# 20_V2X_MODEM.net
KiCad netlist of a schematic drawn in Altium Designer
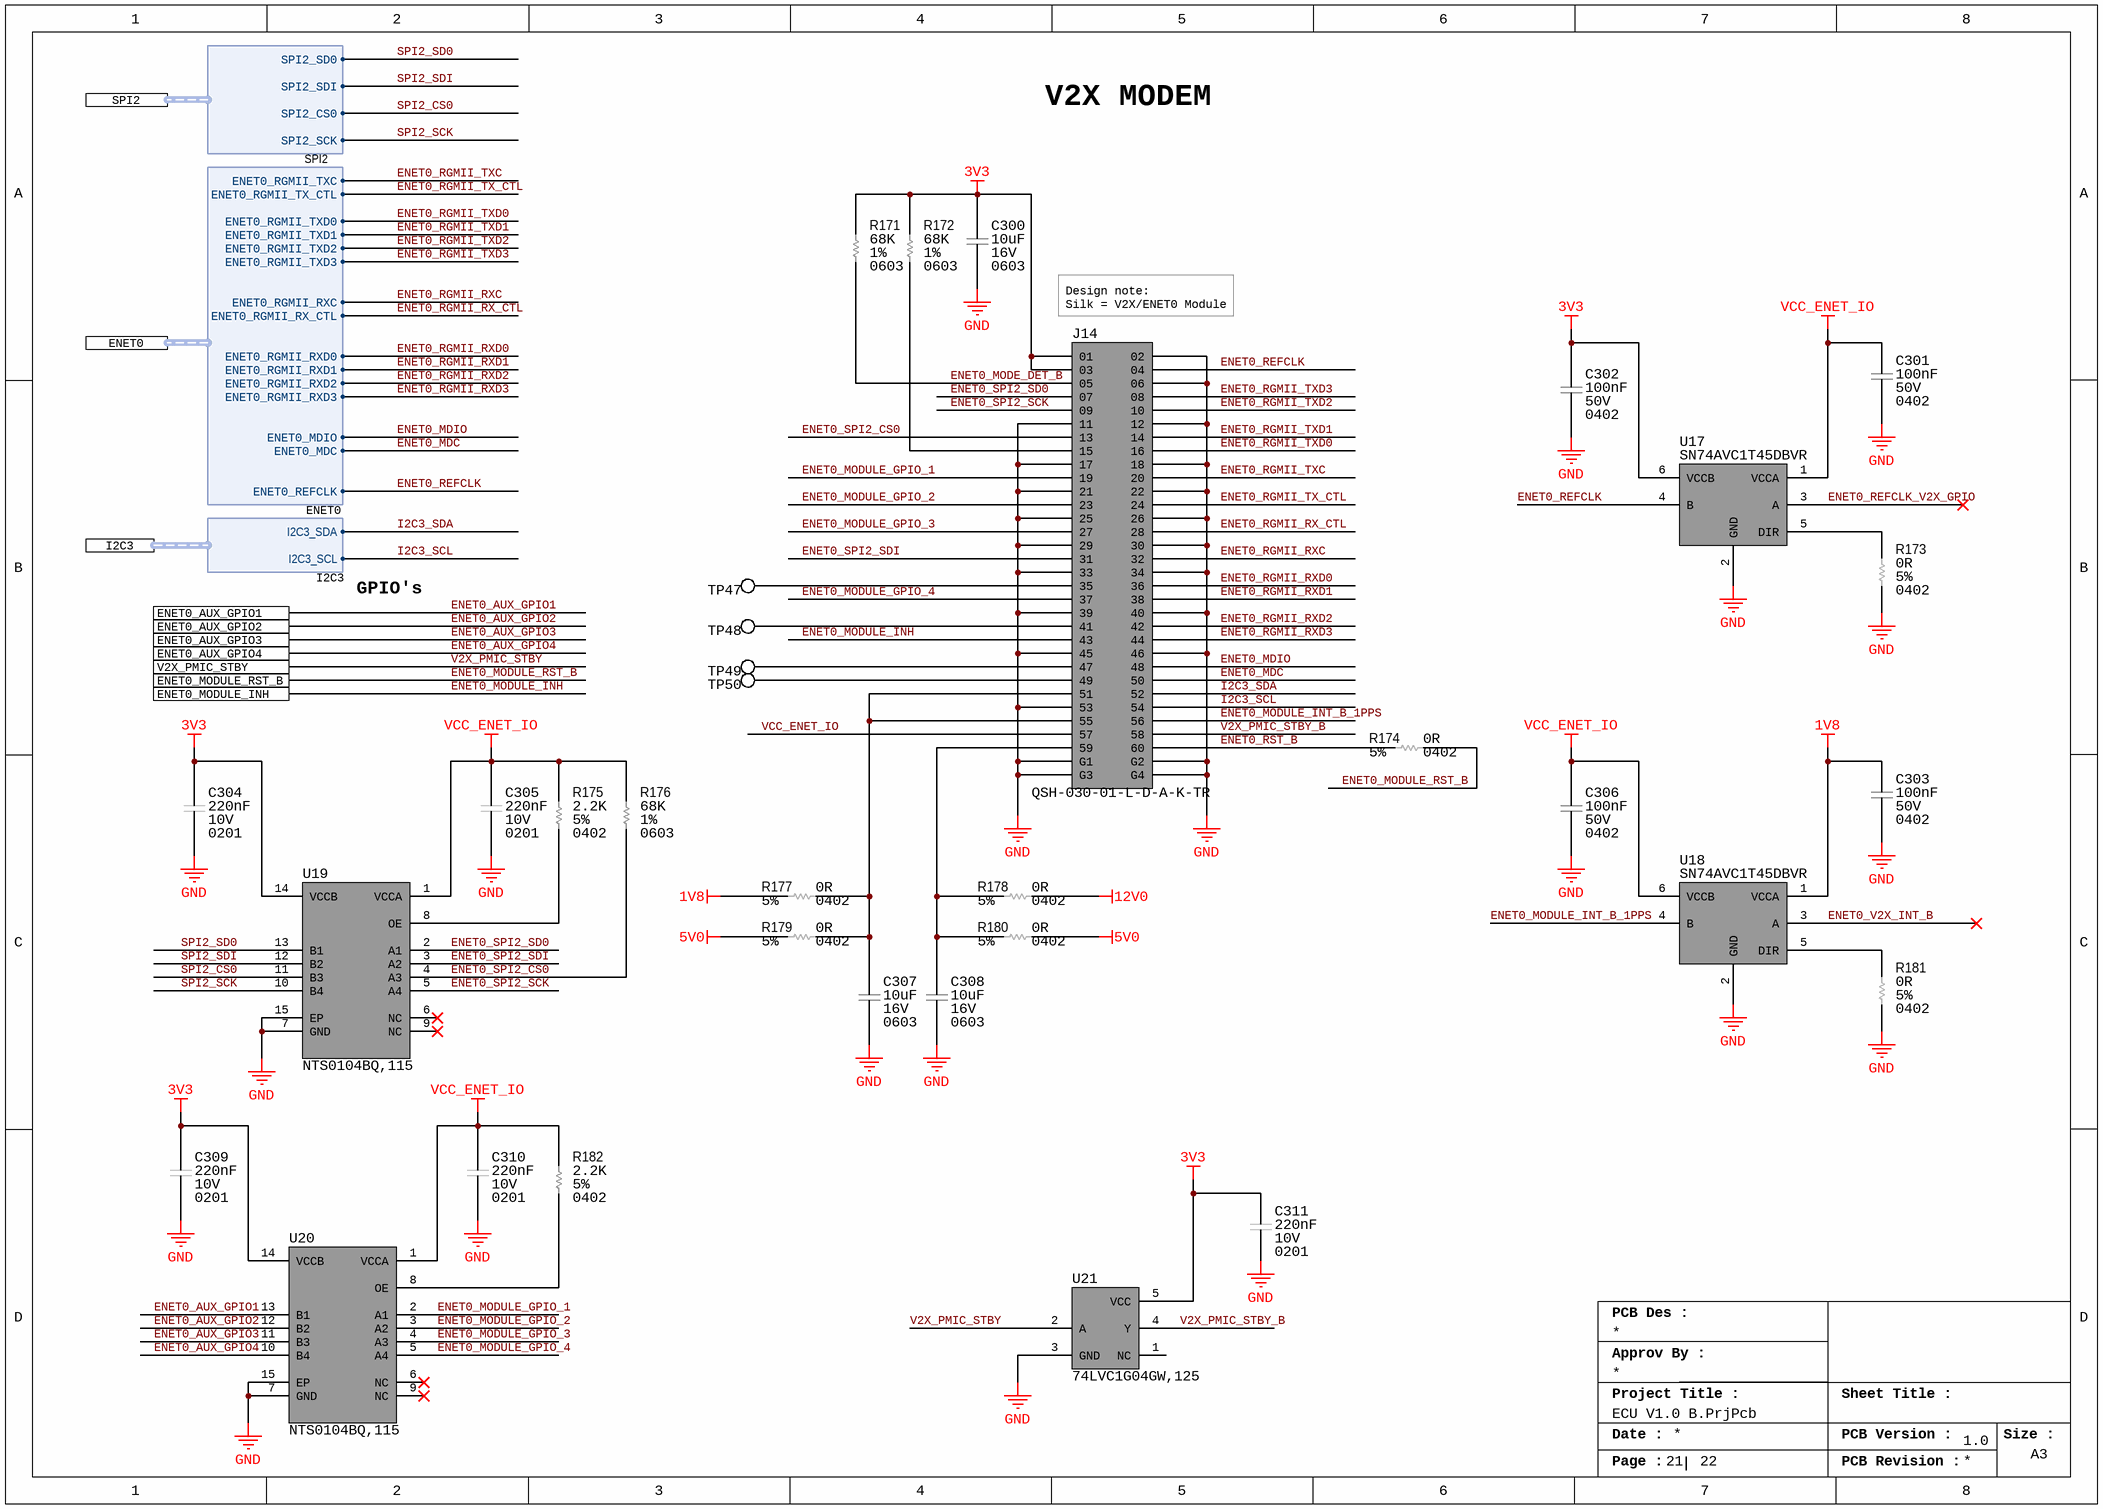
[diagram p0: 20_V2X_MODEM.SchDoc]

(export (version "E")
  (design (tool "Eeschema 10.0.6"))
  (components
    (comp (ref "C300")
      (value "GRM188R61C106MAALD")
      (footprint "CAP_0603_CAPC1608X08N")
      (description "0603 10 uF 16 V ±20% Tolerance X5R Multilayer Ceramic Chip Capacitor")
      (fields
        (field (name "MANUFACTURER") "Murata")
        (field (name "TOLERANCE") "20%")
        (field (name "VOLTAGE RATING") "16V")
        (field (name "CAPACITANCE") "10uF")
        (field (name "CASE/PACKAGE") "0603")
      )
      (libsource (lib "Electronic Devices_LIB") (part "CAP_10UF_16V_X5R_0603"))
    )
    (comp (ref "C301")
      (value "GRM155R71H104KE14D")
      (footprint "CAP_0402_CAPC1005X05N")
      (description "Multilayer Ceramic Capacitor, 0.1 uF, 16 V, ± 10%, X7R, 0402 [1005 Metric]")
      (fields
        (field (name "MANUFACTURER") "Murata")
        (field (name "TOLERANCE") "10%")
        (field (name "VOLTAGE RATING") "50V")
        (field (name "CAPACITANCE") "100nF")
        (field (name "CASE/PACKAGE") "0402")
      )
      (libsource (lib "Electronic Devices_LIB") (part "CAP_100NF_50V_X7R_0402"))
    )
    (comp (ref "C302")
      (value "GRM155R71H104KE14D")
      (footprint "CAP_0402_CAPC1005X05N")
      (description "Multilayer Ceramic Capacitor, 0.1 uF, 16 V, ± 10%, X7R, 0402 [1005 Metric]")
      (fields
        (field (name "MANUFACTURER") "Murata")
        (field (name "TOLERANCE") "10%")
        (field (name "VOLTAGE RATING") "50V")
        (field (name "CAPACITANCE") "100nF")
        (field (name "CASE/PACKAGE") "0402")
      )
      (libsource (lib "Electronic Devices_LIB") (part "CAP_100NF_50V_X7R_0402"))
    )
    (comp (ref "C303")
      (value "GRM155R71H104KE14D")
      (footprint "CAP_0402_CAPC1005X05N")
      (description "Multilayer Ceramic Capacitor, 0.1 uF, 16 V, ± 10%, X7R, 0402 [1005 Metric]")
      (fields
        (field (name "MANUFACTURER") "Murata")
        (field (name "TOLERANCE") "10%")
        (field (name "VOLTAGE RATING") "50V")
        (field (name "CAPACITANCE") "100nF")
        (field (name "CASE/PACKAGE") "0402")
      )
      (libsource (lib "Electronic Devices_LIB") (part "CAP_100NF_50V_X7R_0402"))
    )
    (comp (ref "C304")
      (value "LMK063BJ224MP-F")
      (footprint "CAP_0201_CAPC0603X03N")
      (description "Multilayer Ceramic Capacitors (High dielectric type), 10V, 0.22 uF, ± 20 %, 0201, X5R, RoHS")
      (fields
        (field (name "MANUFACTURER") "Taiyo Yuden")
        (field (name "TOLERANCE") "20%")
        (field (name "VOLTAGE RATING (DC)") "10V")
        (field (name "CAPACITANCE") "220nF")
        (field (name "CASE/PACKAGE") "0201")
      )
      (libsource (lib "Electronic Devices_LIB") (part "CAP_0.22UF_10V_X5R_0201"))
    )
    (comp (ref "C305")
      (value "LMK063BJ224MP-F")
      (footprint "CAP_0201_CAPC0603X03N")
      (description "Multilayer Ceramic Capacitors (High dielectric type), 10V, 0.22 uF, ± 20 %, 0201, X5R, RoHS")
      (fields
        (field (name "MANUFACTURER") "Taiyo Yuden")
        (field (name "TOLERANCE") "20%")
        (field (name "VOLTAGE RATING (DC)") "10V")
        (field (name "CAPACITANCE") "220nF")
        (field (name "CASE/PACKAGE") "0201")
      )
      (libsource (lib "Electronic Devices_LIB") (part "CAP_0.22UF_10V_X5R_0201"))
    )
    (comp (ref "C306")
      (value "GRM155R71H104KE14D")
      (footprint "CAP_0402_CAPC1005X05N")
      (description "Multilayer Ceramic Capacitor, 0.1 uF, 16 V, ± 10%, X7R, 0402 [1005 Metric]")
      (fields
        (field (name "MANUFACTURER") "Murata")
        (field (name "TOLERANCE") "10%")
        (field (name "VOLTAGE RATING") "50V")
        (field (name "CAPACITANCE") "100nF")
        (field (name "CASE/PACKAGE") "0402")
      )
      (libsource (lib "Electronic Devices_LIB") (part "CAP_100NF_50V_X7R_0402"))
    )
    (comp (ref "C307")
      (value "GRM188R61C106MAALD")
      (footprint "CAP_0603_CAPC1608X08N")
      (description "0603 10 uF 16 V ±20% Tolerance X5R Multilayer Ceramic Chip Capacitor")
      (fields
        (field (name "MANUFACTURER") "Murata")
        (field (name "TOLERANCE") "20%")
        (field (name "VOLTAGE RATING") "16V")
        (field (name "CAPACITANCE") "10uF")
        (field (name "CASE/PACKAGE") "0603")
      )
      (libsource (lib "Electronic Devices_LIB") (part "CAP_10UF_16V_X5R_0603"))
    )
    (comp (ref "C308")
      (value "GRM188R61C106MAALD")
      (footprint "CAP_0603_CAPC1608X08N")
      (description "0603 10 uF 16 V ±20% Tolerance X5R Multilayer Ceramic Chip Capacitor")
      (fields
        (field (name "MANUFACTURER") "Murata")
        (field (name "TOLERANCE") "20%")
        (field (name "VOLTAGE RATING") "16V")
        (field (name "CAPACITANCE") "10uF")
        (field (name "CASE/PACKAGE") "0603")
      )
      (libsource (lib "Electronic Devices_LIB") (part "CAP_10UF_16V_X5R_0603"))
    )
    (comp (ref "C309")
      (value "LMK063BJ224MP-F")
      (footprint "CAP_0201_CAPC0603X03N")
      (description "Multilayer Ceramic Capacitors (High dielectric type), 10V, 0.22 uF, ± 20 %, 0201, X5R, RoHS")
      (fields
        (field (name "MANUFACTURER") "Taiyo Yuden")
        (field (name "TOLERANCE") "20%")
        (field (name "VOLTAGE RATING (DC)") "10V")
        (field (name "CAPACITANCE") "220nF")
        (field (name "CASE/PACKAGE") "0201")
      )
      (libsource (lib "Electronic Devices_LIB") (part "CAP_0.22UF_10V_X5R_0201"))
    )
    (comp (ref "C310")
      (value "LMK063BJ224MP-F")
      (footprint "CAP_0201_CAPC0603X03N")
      (description "Multilayer Ceramic Capacitors (High dielectric type), 10V, 0.22 uF, ± 20 %, 0201, X5R, RoHS")
      (fields
        (field (name "MANUFACTURER") "Taiyo Yuden")
        (field (name "TOLERANCE") "20%")
        (field (name "VOLTAGE RATING (DC)") "10V")
        (field (name "CAPACITANCE") "220nF")
        (field (name "CASE/PACKAGE") "0201")
      )
      (libsource (lib "Electronic Devices_LIB") (part "CAP_0.22UF_10V_X5R_0201"))
    )
    (comp (ref "C311")
      (value "LMK063BJ224MP-F")
      (footprint "CAP_0201_CAPC0603X03N")
      (description "Multilayer Ceramic Capacitors (High dielectric type), 10V, 0.22 uF, ± 20 %, 0201, X5R, RoHS")
      (fields
        (field (name "MANUFACTURER") "Taiyo Yuden")
        (field (name "TOLERANCE") "20%")
        (field (name "VOLTAGE RATING (DC)") "10V")
        (field (name "CAPACITANCE") "220nF")
        (field (name "CASE/PACKAGE") "0201")
      )
      (libsource (lib "Electronic Devices_LIB") (part "CAP_0.22UF_10V_X5R_0201"))
    )
    (comp (ref "J14")
      (value "QSH-030-01-L-D-A-K-TR")
      (footprint "SAMTEC_QSH-030-01-X-D-A-XX")
      (description "Board to Board & Mezzanine Connectors 0.50 mm Q Strip High-Speed Ground Plane Socket Strip")
      (fields (field (name "MANUFACTURER") "Samtec"))
      (libsource (lib "Electronic Devices_LIB") (part "CONN_MEZZANINE_60P_0.5mm_QSH-030-01-L-D-A-K-TR"))
    )
    (comp (ref "R171")
      (value "RC0603FR-0768KL")
      (footprint "RES_0603_RESC1608X04N")
      (description "SMD Chip Resistor, 68 kOhm, ± 1%, 100 mW, 0603 [1608 Metric], Thick Film, General Purpose")
      (fields
        (field (name "MANUFACTURER") "Yageo")
        (field (name "TOLERANCE") "1%")
        (field (name "RESISTANCE") "68K")
        (field (name "CASE/PACKAGE") "0603")
      )
      (libsource (lib "Electronic Devices_LIB") (part "RES_68K_1%_100mW_0603"))
    )
    (comp (ref "R172")
      (value "RC0603FR-0768KL")
      (footprint "RES_0603_RESC1608X04N")
      (description "SMD Chip Resistor, 68 kOhm, ± 1%, 100 mW, 0603 [1608 Metric], Thick Film, General Purpose")
      (fields
        (field (name "MANUFACTURER") "Yageo")
        (field (name "TOLERANCE") "1%")
        (field (name "RESISTANCE") "68K")
        (field (name "CASE/PACKAGE") "0603")
      )
      (libsource (lib "Electronic Devices_LIB") (part "RES_68K_1%_100mW_0603"))
    )
    (comp (ref "R173")
      (value "ERJ-2GE0R00X")
      (footprint "RES_0402_RESC1005X04N")
      (description "SMD Chip Resistor, Jumper, 0 ohm, 100 mW, 0402 [1005 Metric], Thick Film, General Purpose")
      (fields
        (field (name "MANUFACTURER") "Panasonic")
        (field (name "CASE CODE (IMPERIAL)") "0402")
        (field (name "TOLERANCE") "5%")
        (field (name "RESISTANCE") "0R")
      )
      (libsource (lib "Electronic Devices_LIB") (part "RES_0R_5%_100mW_0402"))
    )
    (comp (ref "R174")
      (value "ERJ-2GE0R00X")
      (footprint "RES_0402_RESC1005X04N")
      (description "SMD Chip Resistor, Jumper, 0 ohm, 100 mW, 0402 [1005 Metric], Thick Film, General Purpose")
      (fields
        (field (name "MANUFACTURER") "Panasonic")
        (field (name "CASE CODE (IMPERIAL)") "0402")
        (field (name "TOLERANCE") "5%")
        (field (name "RESISTANCE") "0R")
      )
      (libsource (lib "Electronic Devices_LIB") (part "RES_0R_5%_100mW_0402"))
    )
    (comp (ref "R175")
      (value "RC0402JR-072K2L")
      (footprint "RES_0402_RESC1005X04N")
      (description "SMD Chip Resistor, 2.2 kOhm, ± 5%, 63 mW, 0402 [1005 Metric], Thick Film, General Purpose")
      (fields
        (field (name "MANUFACTURER") "Yageo")
        (field (name "TOLERANCE") "5%")
        (field (name "RESISTANCE") "2.2K")
        (field (name "CASE/PACKAGE") "0402")
      )
      (libsource (lib "Electronic Devices_LIB") (part "RES_2.2K_5%_63mW_0402"))
    )
    (comp (ref "R176")
      (value "RC0603FR-0768KL")
      (footprint "RES_0603_RESC1608X04N")
      (description "SMD Chip Resistor, 68 kOhm, ± 1%, 100 mW, 0603 [1608 Metric], Thick Film, General Purpose")
      (fields
        (field (name "MANUFACTURER") "Yageo")
        (field (name "TOLERANCE") "1%")
        (field (name "RESISTANCE") "68K")
        (field (name "CASE/PACKAGE") "0603")
      )
      (libsource (lib "Electronic Devices_LIB") (part "RES_68K_1%_100mW_0603"))
    )
    (comp (ref "R177")
      (value "ERJ-2GE0R00X")
      (footprint "RES_0402_RESC1005X04N")
      (description "SMD Chip Resistor, Jumper, 0 ohm, 100 mW, 0402 [1005 Metric], Thick Film, General Purpose")
      (fields
        (field (name "MANUFACTURER") "Panasonic")
        (field (name "CASE CODE (IMPERIAL)") "0402")
        (field (name "TOLERANCE") "5%")
        (field (name "RESISTANCE") "0R")
      )
      (libsource (lib "Electronic Devices_LIB") (part "RES_0R_5%_100mW_0402"))
    )
    (comp (ref "R178")
      (value "ERJ-2GE0R00X")
      (footprint "RES_0402_RESC1005X04N")
      (description "SMD Chip Resistor, Jumper, 0 ohm, 100 mW, 0402 [1005 Metric], Thick Film, General Purpose")
      (fields
        (field (name "MANUFACTURER") "Panasonic")
        (field (name "CASE CODE (IMPERIAL)") "0402")
        (field (name "TOLERANCE") "5%")
        (field (name "RESISTANCE") "0R")
      )
      (libsource (lib "Electronic Devices_LIB") (part "RES_0R_5%_100mW_0402"))
    )
    (comp (ref "R179")
      (value "ERJ-2GE0R00X")
      (footprint "RES_0402_RESC1005X04N")
      (description "SMD Chip Resistor, Jumper, 0 ohm, 100 mW, 0402 [1005 Metric], Thick Film, General Purpose")
      (fields
        (field (name "MANUFACTURER") "Panasonic")
        (field (name "CASE CODE (IMPERIAL)") "0402")
        (field (name "TOLERANCE") "5%")
        (field (name "RESISTANCE") "0R")
      )
      (libsource (lib "Electronic Devices_LIB") (part "RES_0R_5%_100mW_0402"))
    )
    (comp (ref "R180")
      (value "ERJ-2GE0R00X")
      (footprint "RES_0402_RESC1005X04N")
      (description "SMD Chip Resistor, Jumper, 0 ohm, 100 mW, 0402 [1005 Metric], Thick Film, General Purpose")
      (fields
        (field (name "MANUFACTURER") "Panasonic")
        (field (name "CASE CODE (IMPERIAL)") "0402")
        (field (name "TOLERANCE") "5%")
        (field (name "RESISTANCE") "0R")
      )
      (libsource (lib "Electronic Devices_LIB") (part "RES_0R_5%_100mW_0402"))
    )
    (comp (ref "R181")
      (value "ERJ-2GE0R00X")
      (footprint "RES_0402_RESC1005X04N")
      (description "SMD Chip Resistor, Jumper, 0 ohm, 100 mW, 0402 [1005 Metric], Thick Film, General Purpose")
      (fields
        (field (name "MANUFACTURER") "Panasonic")
        (field (name "CASE CODE (IMPERIAL)") "0402")
        (field (name "TOLERANCE") "5%")
        (field (name "RESISTANCE") "0R")
      )
      (libsource (lib "Electronic Devices_LIB") (part "RES_0R_5%_100mW_0402"))
    )
    (comp (ref "R182")
      (value "RC0402JR-072K2L")
      (footprint "RES_0402_RESC1005X04N")
      (description "SMD Chip Resistor, 2.2 kOhm, ± 5%, 63 mW, 0402 [1005 Metric], Thick Film, General Purpose")
      (fields
        (field (name "MANUFACTURER") "Yageo")
        (field (name "TOLERANCE") "5%")
        (field (name "RESISTANCE") "2.2K")
        (field (name "CASE/PACKAGE") "0402")
      )
      (libsource (lib "Electronic Devices_LIB") (part "RES_2.2K_5%_63mW_0402"))
    )
    (comp (ref "TP47")
      (value "NO COMPONENT")
      (footprint "TP_PAD_0.5MM_SMD_ROUND")
      (description "Test Point, SMD pad, round, 1.5mm, 1.6mm, 3mm diameter")
      (libsource (lib "Electronic Devices_LIB") (part "TP_PAD_SMD_SMALL"))
    )
    (comp (ref "TP48")
      (value "NO COMPONENT")
      (footprint "TP_PAD_0.5MM_SMD_ROUND")
      (description "Test Point, SMD pad, round, 1.5mm, 1.6mm, 3mm diameter")
      (libsource (lib "Electronic Devices_LIB") (part "TP_PAD_SMD_SMALL"))
    )
    (comp (ref "TP49")
      (value "NO COMPONENT")
      (footprint "TP_PAD_0.5MM_SMD_ROUND")
      (description "Test Point, SMD pad, round, 1.5mm, 1.6mm, 3mm diameter")
      (libsource (lib "Electronic Devices_LIB") (part "TP_PAD_SMD_SMALL"))
    )
    (comp (ref "TP50")
      (value "NO COMPONENT")
      (footprint "TP_PAD_0.5MM_SMD_ROUND")
      (description "Test Point, SMD pad, round, 1.5mm, 1.6mm, 3mm diameter")
      (libsource (lib "Electronic Devices_LIB") (part "TP_PAD_SMD_SMALL"))
    )
    (comp (ref "U17")
      (value "SN74AVC1T45DBVR")
      (footprint "SOT95P280X145-6N")
      (description "1.2V~3.6V 1 1 1.2V~3.6V 500Mbps SOT-23-6 Translators / Level Shifters ROHS")
      (fields (field (name "MANUFACTURER") "Texas Instruments"))
      (libsource (lib "Electronic Devices_LIB") (part "IC_LEVEL_TRANSLATE_1CH_SN74AVC1T45DBVR"))
    )
    (comp (ref "U18")
      (value "SN74AVC1T45DBVR")
      (footprint "SOT95P280X145-6N")
      (description "1.2V~3.6V 1 1 1.2V~3.6V 500Mbps SOT-23-6 Translators / Level Shifters ROHS")
      (fields (field (name "MANUFACTURER") "Texas Instruments"))
      (libsource (lib "Electronic Devices_LIB") (part "IC_LEVEL_TRANSLATE_1CH_SN74AVC1T45DBVR"))
    )
    (comp (ref "U19")
      (value "NTS0104BQ,115")
      (footprint "QFN50P300X250X100-15N")
      (description "Voltage Level Translator Bidirectional 1 Circuit 4 Channel 50Mbps 14-DHVQFN (2.5x3)")
      (fields (field (name "MANUFACTURER") "NXP Semiconductors"))
      (libsource (lib "Electronic Devices_LIB") (part "IC_LEVEL_TRASLATE_4CH_NTS0104BQ,115"))
    )
    (comp (ref "U20")
      (value "NTS0104BQ,115")
      (footprint "QFN50P300X250X100-15N")
      (description "Voltage Level Translator Bidirectional 1 Circuit 4 Channel 50Mbps 14-DHVQFN (2.5x3)")
      (fields (field (name "MANUFACTURER") "NXP Semiconductors"))
      (libsource (lib "Electronic Devices_LIB") (part "IC_LEVEL_TRASLATE_4CH_NTS0104BQ,115"))
    )
    (comp (ref "U21")
      (value "74LVC1G04GW,125")
      (footprint "SOT65P210X110-5N")
      (description "74LVC Series 5.5 V Surface Mount Single Inverting Buffer - TSSOP-5")
      (fields (field (name "MANUFACTURER") "Nexperia"))
      (libsource (lib "Electronic Devices_LIB") (part "IC_INVERTER_1CH_74LVC1G04GW,125"))
    )
  )
  (nets
    (net (code "4") (name "/ENET0_AUX_GPIO1") (class "Default")
      (node (ref "U20") (pin "13") (pinfunction "B1_13") (pintype "passive"))
    )
    (net (code "5") (name "/ENET0_AUX_GPIO2") (class "Default")
      (node (ref "U20") (pin "12") (pinfunction "B2_12") (pintype "passive"))
    )
    (net (code "6") (name "/ENET0_AUX_GPIO3") (class "Default")
      (node (ref "U20") (pin "11") (pinfunction "B3_11") (pintype "passive"))
    )
    (net (code "7") (name "/ENET0_AUX_GPIO4") (class "Default")
      (node (ref "U20") (pin "10") (pinfunction "B4_10") (pintype "passive"))
    )
    (net (code "8") (name "/ENET0_MDC") (class "Default")
      (node (ref "J14") (pin "50") (pinfunction "50_50") (pintype "passive"))
    )
    (net (code "9") (name "/ENET0_MDIO") (class "Default")
      (node (ref "J14") (pin "48") (pinfunction "48_48") (pintype "passive"))
    )
    (net (code "10") (name "/ENET0_MODE_DET_B") (class "Default")
      (node (ref "J14") (pin "05") (pinfunction "05_05") (pintype "passive"))
      (node (ref "R171") (pin "1") (pinfunction "1_1") (pintype "passive"))
    )
    (net (code "11") (name "/ENET0_MODULE_GPIO_1") (class "Default")
      (node (ref "J14") (pin "19") (pinfunction "19_19") (pintype "passive"))
      (node (ref "U20") (pin "2") (pinfunction "A1_2") (pintype "passive"))
    )
    (net (code "12") (name "/ENET0_MODULE_GPIO_2") (class "Default")
      (node (ref "J14") (pin "23") (pinfunction "23_23") (pintype "passive"))
      (node (ref "U20") (pin "3") (pinfunction "A2_3") (pintype "passive"))
    )
    (net (code "13") (name "/ENET0_MODULE_GPIO_3") (class "Default")
      (node (ref "J14") (pin "27") (pinfunction "27_27") (pintype "passive"))
      (node (ref "U20") (pin "4") (pinfunction "A3_4") (pintype "passive"))
    )
    (net (code "14") (name "/ENET0_MODULE_GPIO_4") (class "Default")
      (node (ref "J14") (pin "37") (pinfunction "37_37") (pintype "passive"))
      (node (ref "U20") (pin "5") (pinfunction "A4_5") (pintype "passive"))
    )
    (net (code "15") (name "/ENET0_MODULE_INH") (class "Default")
      (node (ref "J14") (pin "43") (pinfunction "43_43") (pintype "passive"))
    )
    (net (code "16") (name "/ENET0_MODULE_INT_B_1PPS") (class "Default")
      (node (ref "J14") (pin "56") (pinfunction "56_56") (pintype "passive"))
      (node (ref "U18") (pin "4") (pinfunction "B_4") (pintype "passive"))
    )
    (net (code "17") (name "/ENET0_MODULE_RST_B") (class "Default")
      (node (ref "R174") (pin "2") (pinfunction "2_2") (pintype "passive"))
    )
    (net (code "18") (name "/ENET0_REFCLK") (class "Default")
      (node (ref "J14") (pin "04") (pinfunction "04_04") (pintype "passive"))
      (node (ref "U17") (pin "4") (pinfunction "B_4") (pintype "passive"))
    )
    (net (code "19") (name "/ENET0_REFCLK_V2X_GPIO") (class "Default")
      (node (ref "U17") (pin "3") (pinfunction "A_3") (pintype "passive+no_connect"))
    )
    (net (code "20") (name "/ENET0_RGMII_RXC") (class "Default")
      (node (ref "J14") (pin "32") (pinfunction "32_32") (pintype "passive"))
    )
    (net (code "21") (name "/ENET0_RGMII_RXD0") (class "Default")
      (node (ref "J14") (pin "36") (pinfunction "36_36") (pintype "passive"))
    )
    (net (code "22") (name "/ENET0_RGMII_RXD1") (class "Default")
      (node (ref "J14") (pin "38") (pinfunction "38_38") (pintype "passive"))
    )
    (net (code "23") (name "/ENET0_RGMII_RXD2") (class "Default")
      (node (ref "J14") (pin "42") (pinfunction "42_42") (pintype "passive"))
    )
    (net (code "24") (name "/ENET0_RGMII_RXD3") (class "Default")
      (node (ref "J14") (pin "44") (pinfunction "44_44") (pintype "passive"))
    )
    (net (code "25") (name "/ENET0_RGMII_RX_CTL") (class "Default")
      (node (ref "J14") (pin "28") (pinfunction "28_28") (pintype "passive"))
    )
    (net (code "26") (name "/ENET0_RGMII_TXC") (class "Default")
      (node (ref "J14") (pin "20") (pinfunction "20_20") (pintype "passive"))
    )
    (net (code "27") (name "/ENET0_RGMII_TXD0") (class "Default")
      (node (ref "J14") (pin "16") (pinfunction "16_16") (pintype "passive"))
    )
    (net (code "28") (name "/ENET0_RGMII_TXD1") (class "Default")
      (node (ref "J14") (pin "14") (pinfunction "14_14") (pintype "passive"))
    )
    (net (code "29") (name "/ENET0_RGMII_TXD2") (class "Default")
      (node (ref "J14") (pin "10") (pinfunction "10_10") (pintype "passive"))
    )
    (net (code "30") (name "/ENET0_RGMII_TXD3") (class "Default")
      (node (ref "J14") (pin "08") (pinfunction "08_08") (pintype "passive"))
    )
    (net (code "31") (name "/ENET0_RGMII_TX_CTL") (class "Default")
      (node (ref "J14") (pin "24") (pinfunction "24_24") (pintype "passive"))
    )
    (net (code "32") (name "/ENET0_RST_B") (class "Default")
      (node (ref "J14") (pin "60") (pinfunction "60_60") (pintype "passive"))
      (node (ref "R174") (pin "1") (pinfunction "1_1") (pintype "passive"))
    )
    (net (code "33") (name "/ENET0_SPI2_CS0") (class "Default")
      (node (ref "J14") (pin "13") (pinfunction "13_13") (pintype "passive"))
      (node (ref "R176") (pin "1") (pinfunction "1_1") (pintype "passive"))
      (node (ref "U19") (pin "4") (pinfunction "A3_4") (pintype "passive"))
    )
    (net (code "34") (name "/ENET0_SPI2_SCK") (class "Default")
      (node (ref "J14") (pin "09") (pinfunction "09_09") (pintype "passive"))
      (node (ref "U19") (pin "5") (pinfunction "A4_5") (pintype "passive"))
    )
    (net (code "35") (name "/ENET0_SPI2_SD0") (class "Default")
      (node (ref "J14") (pin "07") (pinfunction "07_07") (pintype "passive"))
      (node (ref "U19") (pin "2") (pinfunction "A1_2") (pintype "passive"))
    )
    (net (code "36") (name "/ENET0_SPI2_SDI") (class "Default")
      (node (ref "J14") (pin "31") (pinfunction "31_31") (pintype "passive"))
      (node (ref "U19") (pin "3") (pinfunction "A2_3") (pintype "passive"))
    )
    (net (code "37") (name "/ENET0_V2X_INT_B") (class "Default")
      (node (ref "U18") (pin "3") (pinfunction "A_3") (pintype "passive+no_connect"))
    )
    (net (code "38") (name "/I2C3_SCL") (class "Default")
      (node (ref "J14") (pin "54") (pinfunction "54_54") (pintype "passive"))
    )
    (net (code "39") (name "/I2C3_SDA") (class "Default")
      (node (ref "J14") (pin "52") (pinfunction "52_52") (pintype "passive"))
    )
    (net (code "40") (name "/SPI2_CS0") (class "Default")
      (node (ref "U19") (pin "11") (pinfunction "B3_11") (pintype "passive"))
    )
    (net (code "41") (name "/SPI2_SCK") (class "Default")
      (node (ref "U19") (pin "10") (pinfunction "B4_10") (pintype "passive"))
    )
    (net (code "42") (name "/SPI2_SD0") (class "Default")
      (node (ref "U19") (pin "13") (pinfunction "B1_13") (pintype "passive"))
    )
    (net (code "43") (name "/SPI2_SDI") (class "Default")
      (node (ref "U19") (pin "12") (pinfunction "B2_12") (pintype "passive"))
    )
    (net (code "44") (name "/V2X_PMIC_STBY") (class "Default")
      (node (ref "U21") (pin "2") (pinfunction "A_2") (pintype "passive"))
    )
    (net (code "45") (name "/V2X_PMIC_STBY_B") (class "Default")
      (node (ref "J14") (pin "58") (pinfunction "58_58") (pintype "passive"))
      (node (ref "U21") (pin "4") (pinfunction "Y_4") (pintype "passive"))
    )
    (net (code "49") (name "1V8") (class "Default")
      (node (ref "C303") (pin "2") (pinfunction "2_2") (pintype "passive"))
      (node (ref "R177") (pin "1") (pinfunction "1_1") (pintype "passive"))
      (node (ref "U18") (pin "1") (pinfunction "VCCA_1") (pintype "power_in"))
    )
    (net (code "50") (name "3V3") (class "Default")
      (node (ref "C300") (pin "2") (pinfunction "2_2") (pintype "passive"))
      (node (ref "C302") (pin "2") (pinfunction "2_2") (pintype "passive"))
      (node (ref "C304") (pin "1") (pinfunction "1_1") (pintype "passive"))
      (node (ref "C309") (pin "1") (pinfunction "1_1") (pintype "passive"))
      (node (ref "C311") (pin "1") (pinfunction "1_1") (pintype "passive"))
      (node (ref "J14") (pin "01") (pinfunction "01_01") (pintype "passive"))
      (node (ref "J14") (pin "03") (pinfunction "03_03") (pintype "passive"))
      (node (ref "R171") (pin "2") (pinfunction "2_2") (pintype "passive"))
      (node (ref "R172") (pin "2") (pinfunction "2_2") (pintype "passive"))
      (node (ref "U17") (pin "6") (pinfunction "VCCB_6") (pintype "power_in"))
      (node (ref "U19") (pin "14") (pinfunction "VCCB_14") (pintype "power_in"))
      (node (ref "U20") (pin "14") (pinfunction "VCCB_14") (pintype "power_in"))
      (node (ref "U21") (pin "5") (pinfunction "VCC_5") (pintype "power_in"))
    )
    (net (code "51") (name "5V0") (class "Default")
      (node (ref "R179") (pin "1") (pinfunction "1_1") (pintype "passive"))
      (node (ref "R180") (pin "2") (pinfunction "2_2") (pintype "passive"))
    )
    (net (code "52") (name "12V0") (class "Default")
      (node (ref "R178") (pin "2") (pinfunction "2_2") (pintype "passive"))
    )
    (net (code "53") (name "GND") (class "Default")
      (node (ref "C300") (pin "1") (pinfunction "1_1") (pintype "passive"))
      (node (ref "C301") (pin "1") (pinfunction "1_1") (pintype "passive"))
      (node (ref "C302") (pin "1") (pinfunction "1_1") (pintype "passive"))
      (node (ref "C303") (pin "1") (pinfunction "1_1") (pintype "passive"))
      (node (ref "C304") (pin "2") (pinfunction "2_2") (pintype "passive"))
      (node (ref "C305") (pin "2") (pinfunction "2_2") (pintype "passive"))
      (node (ref "C306") (pin "1") (pinfunction "1_1") (pintype "passive"))
      (node (ref "C307") (pin "1") (pinfunction "1_1") (pintype "passive"))
      (node (ref "C308") (pin "1") (pinfunction "1_1") (pintype "passive"))
      (node (ref "C309") (pin "2") (pinfunction "2_2") (pintype "passive"))
      (node (ref "C310") (pin "2") (pinfunction "2_2") (pintype "passive"))
      (node (ref "C311") (pin "2") (pinfunction "2_2") (pintype "passive"))
      (node (ref "J14") (pin "02") (pinfunction "02_02") (pintype "passive"))
      (node (ref "J14") (pin "06") (pinfunction "06_06") (pintype "passive"))
      (node (ref "J14") (pin "11") (pinfunction "11_11") (pintype "passive"))
      (node (ref "J14") (pin "12") (pinfunction "12_12") (pintype "passive"))
      (node (ref "J14") (pin "17") (pinfunction "17_17") (pintype "passive"))
      (node (ref "J14") (pin "18") (pinfunction "18_18") (pintype "passive"))
      (node (ref "J14") (pin "21") (pinfunction "21_21") (pintype "passive"))
      (node (ref "J14") (pin "22") (pinfunction "22_22") (pintype "passive"))
      (node (ref "J14") (pin "25") (pinfunction "25_25") (pintype "passive"))
      (node (ref "J14") (pin "26") (pinfunction "26_26") (pintype "passive"))
      (node (ref "J14") (pin "29") (pinfunction "29_29") (pintype "passive"))
      (node (ref "J14") (pin "30") (pinfunction "30_30") (pintype "passive"))
      (node (ref "J14") (pin "33") (pinfunction "33_33") (pintype "passive"))
      (node (ref "J14") (pin "34") (pinfunction "34_34") (pintype "passive"))
      (node (ref "J14") (pin "39") (pinfunction "39_39") (pintype "passive"))
      (node (ref "J14") (pin "40") (pinfunction "40_40") (pintype "passive"))
      (node (ref "J14") (pin "45") (pinfunction "45_45") (pintype "passive"))
      (node (ref "J14") (pin "46") (pinfunction "46_46") (pintype "passive"))
      (node (ref "J14") (pin "53") (pinfunction "53_53") (pintype "passive"))
      (node (ref "J14") (pin "G1") (pinfunction "G1_G1") (pintype "power_in"))
      (node (ref "J14") (pin "G2") (pinfunction "G2_G2") (pintype "power_in"))
      (node (ref "J14") (pin "G3") (pinfunction "G3_G3") (pintype "power_in"))
      (node (ref "J14") (pin "G4") (pinfunction "G4_G4") (pintype "power_in"))
      (node (ref "R173") (pin "1") (pinfunction "1_1") (pintype "passive"))
      (node (ref "R181") (pin "1") (pinfunction "1_1") (pintype "passive"))
      (node (ref "U17") (pin "2") (pinfunction "GND_2") (pintype "power_in"))
      (node (ref "U18") (pin "2") (pinfunction "GND_2") (pintype "power_in"))
      (node (ref "U19") (pin "15") (pinfunction "EP_15") (pintype "passive"))
      (node (ref "U19") (pin "7") (pinfunction "GND_7") (pintype "power_in"))
      (node (ref "U20") (pin "15") (pinfunction "EP_15") (pintype "passive"))
      (node (ref "U20") (pin "7") (pinfunction "GND_7") (pintype "power_in"))
      (node (ref "U21") (pin "3") (pinfunction "GND_3") (pintype "power_in"))
    )
    (net (code "54") (name "Net-(C307-Pad2)") (class "Default")
      (node (ref "C307") (pin "2") (pinfunction "2_2") (pintype "passive"))
      (node (ref "J14") (pin "51") (pinfunction "51_51") (pintype "passive"))
      (node (ref "J14") (pin "55") (pinfunction "55_55") (pintype "passive"))
      (node (ref "R177") (pin "2") (pinfunction "2_2") (pintype "passive"))
      (node (ref "R179") (pin "2") (pinfunction "2_2") (pintype "passive"))
    )
    (net (code "55") (name "Net-(C308-Pad2)") (class "Default")
      (node (ref "C308") (pin "2") (pinfunction "2_2") (pintype "passive"))
      (node (ref "J14") (pin "59") (pinfunction "59_59") (pintype "passive"))
      (node (ref "R178") (pin "1") (pinfunction "1_1") (pintype "passive"))
      (node (ref "R180") (pin "1") (pinfunction "1_1") (pintype "passive"))
    )
    (net (code "56") (name "Net-(J14-Pad15)") (class "Default")
      (node (ref "J14") (pin "15") (pinfunction "15_15") (pintype "passive"))
      (node (ref "R172") (pin "1") (pinfunction "1_1") (pintype "passive"))
    )
    (net (code "57") (name "Net-(J14-Pad35)") (class "Default")
      (node (ref "J14") (pin "35") (pinfunction "35_35") (pintype "passive"))
      (node (ref "TP47") (pin "1") (pinfunction "1_1") (pintype "passive"))
    )
    (net (code "58") (name "Net-(J14-Pad41)") (class "Default")
      (node (ref "J14") (pin "41") (pinfunction "41_41") (pintype "passive"))
      (node (ref "TP48") (pin "1") (pinfunction "1_1") (pintype "passive"))
    )
    (net (code "59") (name "Net-(J14-Pad47)") (class "Default")
      (node (ref "J14") (pin "47") (pinfunction "47_47") (pintype "passive"))
      (node (ref "TP49") (pin "1") (pinfunction "1_1") (pintype "passive"))
    )
    (net (code "60") (name "Net-(J14-Pad49)") (class "Default")
      (node (ref "J14") (pin "49") (pinfunction "49_49") (pintype "passive"))
      (node (ref "TP50") (pin "1") (pinfunction "1_1") (pintype "passive"))
    )
    (net (code "61") (name "Net-(U17-DIR)") (class "Default")
      (node (ref "R173") (pin "2") (pinfunction "2_2") (pintype "passive"))
      (node (ref "U17") (pin "5") (pinfunction "DIR_5") (pintype "passive"))
    )
    (net (code "62") (name "Net-(U18-DIR)") (class "Default")
      (node (ref "R181") (pin "2") (pinfunction "2_2") (pintype "passive"))
      (node (ref "U18") (pin "5") (pinfunction "DIR_5") (pintype "passive"))
    )
    (net (code "63") (name "Net-(U19-OE)") (class "Default")
      (node (ref "R175") (pin "1") (pinfunction "1_1") (pintype "passive"))
      (node (ref "U19") (pin "8") (pinfunction "OE_8") (pintype "passive"))
    )
    (net (code "64") (name "Net-(U20-OE)") (class "Default")
      (node (ref "R182") (pin "1") (pinfunction "1_1") (pintype "passive"))
      (node (ref "U20") (pin "8") (pinfunction "OE_8") (pintype "passive"))
    )
    (net (code "65") (name "VCC_ENET_IO") (class "Default")
      (node (ref "C301") (pin "2") (pinfunction "2_2") (pintype "passive"))
      (node (ref "C305") (pin "1") (pinfunction "1_1") (pintype "passive"))
      (node (ref "C306") (pin "2") (pinfunction "2_2") (pintype "passive"))
      (node (ref "C310") (pin "1") (pinfunction "1_1") (pintype "passive"))
      (node (ref "J14") (pin "57") (pinfunction "57_57") (pintype "passive"))
      (node (ref "R175") (pin "2") (pinfunction "2_2") (pintype "passive"))
      (node (ref "R176") (pin "2") (pinfunction "2_2") (pintype "passive"))
      (node (ref "R182") (pin "2") (pinfunction "2_2") (pintype "passive"))
      (node (ref "U17") (pin "1") (pinfunction "VCCA_1") (pintype "power_in"))
      (node (ref "U18") (pin "6") (pinfunction "VCCB_6") (pintype "power_in"))
      (node (ref "U19") (pin "1") (pinfunction "VCCA_1") (pintype "power_in"))
      (node (ref "U20") (pin "1") (pinfunction "VCCA_1") (pintype "power_in"))
    )
    (net (code "66") (name "unconnected-(U19-NC-Pad6)") (class "Default")
      (node (ref "U19") (pin "6") (pinfunction "NC_6") (pintype "passive+no_connect"))
    )
    (net (code "67") (name "unconnected-(U19-NC-Pad9)") (class "Default")
      (node (ref "U19") (pin "9") (pinfunction "NC_9") (pintype "passive+no_connect"))
    )
    (net (code "68") (name "unconnected-(U20-NC-Pad6)") (class "Default")
      (node (ref "U20") (pin "6") (pinfunction "NC_6") (pintype "passive+no_connect"))
    )
    (net (code "69") (name "unconnected-(U20-NC-Pad9)") (class "Default")
      (node (ref "U20") (pin "9") (pinfunction "NC_9") (pintype "passive+no_connect"))
    )
    (net (code "70") (name "unconnected-(U21-NC-Pad1)") (class "Default")
      (node (ref "U21") (pin "1") (pinfunction "NC_1") (pintype "passive"))
    )
  )
)
